# 7segLED.net
KiCad netlist of a schematic drawn in Altium Designer
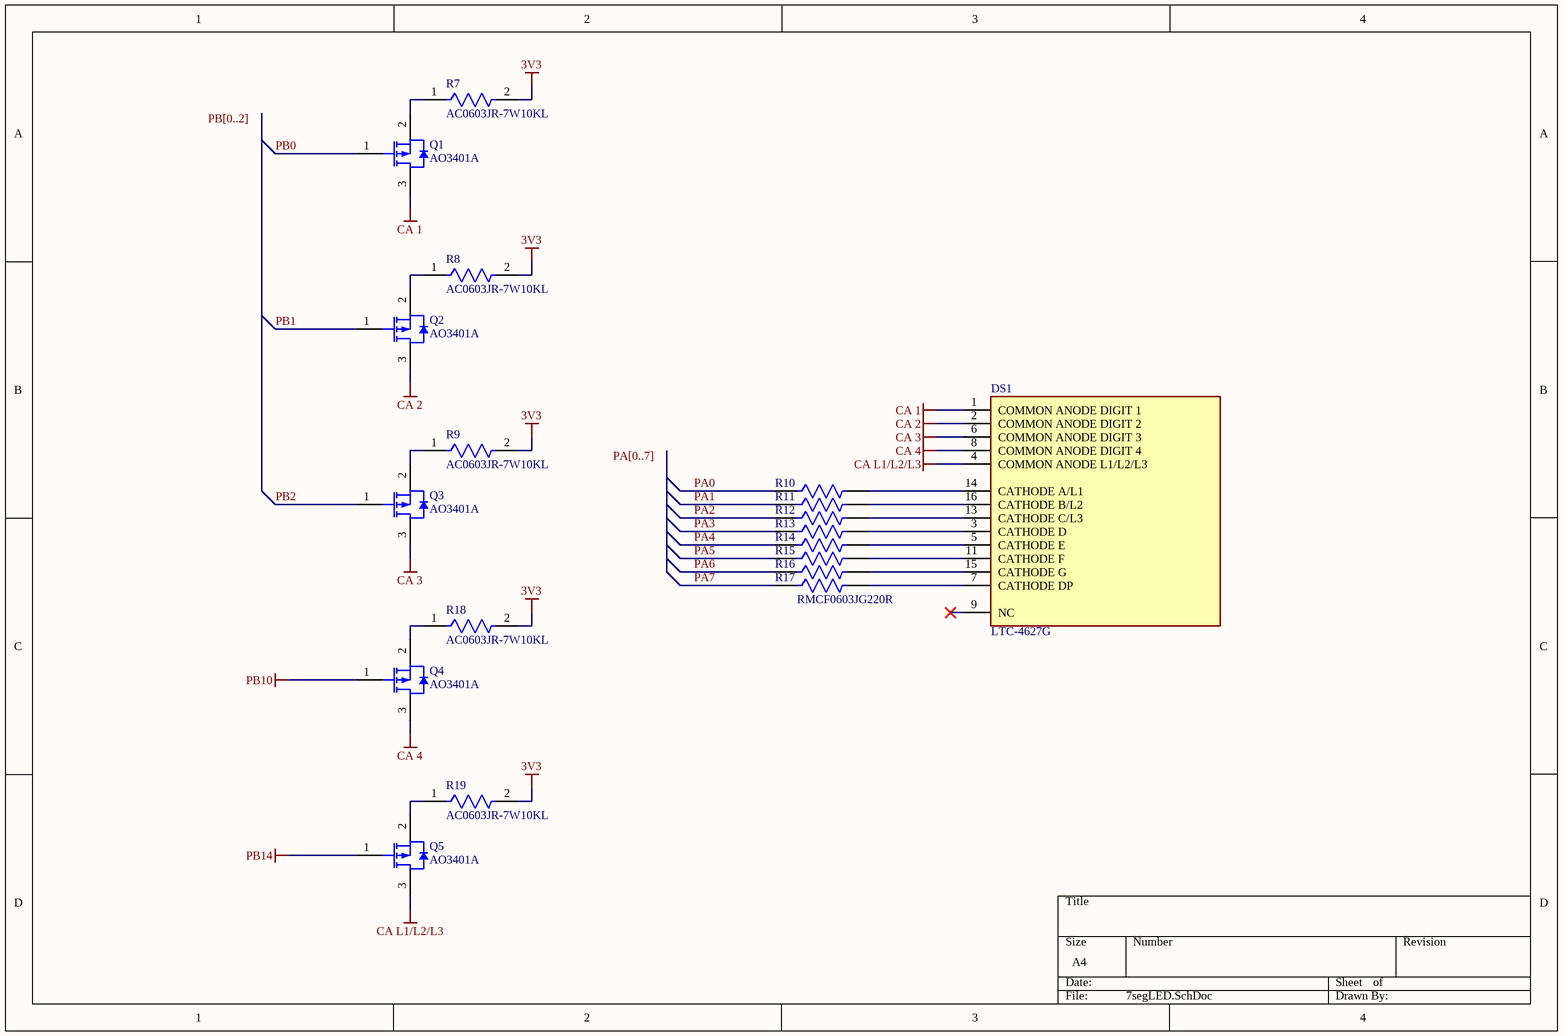
[diagram p0: 7segLED.SchDoc]

(export (version "E")
  (design (tool "Eeschema 10.0.6"))
  (components
    (comp (ref "DS1")
      (value "LTC-4627G")
      (footprint "FP-LTC-4627G-MFG")
      (description "LED 7-SEG 4DIGIT GRN 0.4\" CA")
      (fields
        (field (name "OCTOPART") "https://octopart.com/ltc-4627g-lite-on-8442722")
        (field (name "MANUFACTURER") "Lite-On")
      )
      (libsource (lib "Altium Content Vault") (part "4d055b40ff5d7e2a8d2cf02d3223e38"))
    )
    (comp (ref "Q1")
      (value "AO3401A")
      (footprint "AO-SOT-23-3L_V")
      (description "P-Channel MOSFET, 30 V, 4 A, -55 to 150 degC, 3-Pin SOT-23-3L, RoHS, Tape and Reel")
      (fields (field (name "MANUFACTURER") "Alpha and Omega"))
      (libsource (lib "Altium Content Vault") (part "PEMOS-GSD-3"))
    )
    (comp (ref "Q2")
      (value "AO3401A")
      (footprint "AO-SOT-23-3L_V")
      (description "P-Channel MOSFET, 30 V, 4 A, -55 to 150 degC, 3-Pin SOT-23-3L, RoHS, Tape and Reel")
      (fields (field (name "MANUFACTURER") "Alpha and Omega"))
      (libsource (lib "Altium Content Vault") (part "PEMOS-GSD-3"))
    )
    (comp (ref "Q3")
      (value "AO3401A")
      (footprint "AO-SOT-23-3L_V")
      (description "P-Channel MOSFET, 30 V, 4 A, -55 to 150 degC, 3-Pin SOT-23-3L, RoHS, Tape and Reel")
      (fields (field (name "MANUFACTURER") "Alpha and Omega"))
      (libsource (lib "Altium Content Vault") (part "PEMOS-GSD-3"))
    )
    (comp (ref "Q4")
      (value "AO3401A")
      (footprint "AO-SOT-23-3L_V")
      (description "P-Channel MOSFET, 30 V, 4 A, -55 to 150 degC, 3-Pin SOT-23-3L, RoHS, Tape and Reel")
      (fields (field (name "MANUFACTURER") "Alpha and Omega"))
      (libsource (lib "Altium Content Vault") (part "PEMOS-GSD-3"))
    )
    (comp (ref "Q5")
      (value "AO3401A")
      (footprint "AO-SOT-23-3L_V")
      (description "P-Channel MOSFET, 30 V, 4 A, -55 to 150 degC, 3-Pin SOT-23-3L, RoHS, Tape and Reel")
      (fields (field (name "MANUFACTURER") "Alpha and Omega"))
      (libsource (lib "Altium Content Vault") (part "PEMOS-GSD-3"))
    )
    (comp (ref "R7")
      (value "AC0603JR-7W10KL")
      (footprint "FP-AC0603-IPC_A")
      (description "RES 10kΩ 5.00% 0.2W 0603")
      (libsource (lib "") (part "1029c3af85768c4190bb7ad29bc67b5_1"))
    )
    (comp (ref "R8")
      (value "AC0603JR-7W10KL")
      (footprint "FP-AC0603-IPC_A")
      (description "RES 10kΩ 5.00% 0.2W 0603")
      (libsource (lib "") (part "1029c3af85768c4190bb7ad29bc67b5_1"))
    )
    (comp (ref "R9")
      (value "AC0603JR-7W10KL")
      (footprint "FP-AC0603-IPC_A")
      (description "RES 10kΩ 5.00% 0.2W 0603")
      (libsource (lib "") (part "1029c3af85768c4190bb7ad29bc67b5_1"))
    )
    (comp (ref "R10")
      (value "RMCF0603JG220R")
      (footprint "FP-RMCF0603-MFG")
      (description "220Ω ±5% 0.1W 0603 Thick Film Chip Resistor AEC-Q200 compliant")
      (fields (field (name "TOLERANCE") "5%"))
      (libsource (lib "Altium Content Vault") (part "1029c3af85768c4190bb7ad29bc67b5"))
    )
    (comp (ref "R11")
      (value "RMCF0603JG220R")
      (footprint "FP-RMCF0603-MFG")
      (description "220Ω ±5% 0.1W 0603 Thick Film Chip Resistor AEC-Q200 compliant")
      (fields (field (name "TOLERANCE") "5%"))
      (libsource (lib "Altium Content Vault") (part "1029c3af85768c4190bb7ad29bc67b5"))
    )
    (comp (ref "R12")
      (value "RMCF0603JG220R")
      (footprint "FP-RMCF0603-MFG")
      (description "220Ω ±5% 0.1W 0603 Thick Film Chip Resistor AEC-Q200 compliant")
      (fields (field (name "TOLERANCE") "5%"))
      (libsource (lib "Altium Content Vault") (part "1029c3af85768c4190bb7ad29bc67b5"))
    )
    (comp (ref "R13")
      (value "RMCF0603JG220R")
      (footprint "FP-RMCF0603-MFG")
      (description "220Ω ±5% 0.1W 0603 Thick Film Chip Resistor AEC-Q200 compliant")
      (fields (field (name "TOLERANCE") "5%"))
      (libsource (lib "Altium Content Vault") (part "1029c3af85768c4190bb7ad29bc67b5"))
    )
    (comp (ref "R14")
      (value "RMCF0603JG220R")
      (footprint "FP-RMCF0603-MFG")
      (description "220Ω ±5% 0.1W 0603 Thick Film Chip Resistor AEC-Q200 compliant")
      (fields (field (name "TOLERANCE") "5%"))
      (libsource (lib "Altium Content Vault") (part "1029c3af85768c4190bb7ad29bc67b5"))
    )
    (comp (ref "R15")
      (value "RMCF0603JG220R")
      (footprint "FP-RMCF0603-MFG")
      (description "220Ω ±5% 0.1W 0603 Thick Film Chip Resistor AEC-Q200 compliant")
      (fields (field (name "TOLERANCE") "5%"))
      (libsource (lib "Altium Content Vault") (part "1029c3af85768c4190bb7ad29bc67b5"))
    )
    (comp (ref "R16")
      (value "RMCF0603JG220R")
      (footprint "FP-RMCF0603-MFG")
      (description "220Ω ±5% 0.1W 0603 Thick Film Chip Resistor AEC-Q200 compliant")
      (fields (field (name "TOLERANCE") "5%"))
      (libsource (lib "Altium Content Vault") (part "1029c3af85768c4190bb7ad29bc67b5"))
    )
    (comp (ref "R17")
      (value "RMCF0603JG220R")
      (footprint "FP-RMCF0603-MFG")
      (description "220Ω ±5% 0.1W 0603 Thick Film Chip Resistor AEC-Q200 compliant")
      (fields (field (name "TOLERANCE") "5%"))
      (libsource (lib "Altium Content Vault") (part "1029c3af85768c4190bb7ad29bc67b5"))
    )
    (comp (ref "R18")
      (value "AC0603JR-7W10KL")
      (footprint "FP-AC0603-IPC_A")
      (description "RES 10kΩ 5.00% 0.2W 0603")
      (libsource (lib "") (part "1029c3af85768c4190bb7ad29bc67b5_1"))
    )
    (comp (ref "R19")
      (value "AC0603JR-7W10KL")
      (footprint "FP-AC0603-IPC_A")
      (description "RES 10kΩ 5.00% 0.2W 0603")
      (libsource (lib "") (part "1029c3af85768c4190bb7ad29bc67b5_1"))
    )
  )
  (nets
    (net (code "1") (name "/PA0") (class "Default")
      (node (ref "R10") (pin "1") (pinfunction "1_1") (pintype "passive"))
    )
    (net (code "2") (name "/PA1") (class "Default")
      (node (ref "R11") (pin "1") (pinfunction "1_1") (pintype "passive"))
    )
    (net (code "3") (name "/PA2") (class "Default")
      (node (ref "R12") (pin "1") (pinfunction "1_1") (pintype "passive"))
    )
    (net (code "4") (name "/PA3") (class "Default")
      (node (ref "R13") (pin "1") (pinfunction "1_1") (pintype "passive"))
    )
    (net (code "5") (name "/PA4") (class "Default")
      (node (ref "R14") (pin "1") (pinfunction "1_1") (pintype "passive"))
    )
    (net (code "6") (name "/PA5") (class "Default")
      (node (ref "R15") (pin "1") (pinfunction "1_1") (pintype "passive"))
    )
    (net (code "7") (name "/PA6") (class "Default")
      (node (ref "R16") (pin "1") (pinfunction "1_1") (pintype "passive"))
    )
    (net (code "8") (name "/PA7") (class "Default")
      (node (ref "R17") (pin "1") (pinfunction "1_1") (pintype "passive"))
    )
    (net (code "10") (name "/PB0") (class "Default")
      (node (ref "Q1") (pin "1") (pinfunction "GATE_1") (pintype "passive"))
    )
    (net (code "11") (name "/PB1") (class "Default")
      (node (ref "Q2") (pin "1") (pinfunction "GATE_1") (pintype "passive"))
    )
    (net (code "12") (name "/PB2") (class "Default")
      (node (ref "Q3") (pin "1") (pinfunction "GATE_1") (pintype "passive"))
    )
    (net (code "14") (name "3V3") (class "Default")
      (node (ref "R18") (pin "2") (pinfunction "2_2") (pintype "passive"))
      (node (ref "R19") (pin "2") (pinfunction "2_2") (pintype "passive"))
      (node (ref "R7") (pin "2") (pinfunction "2_2") (pintype "passive"))
      (node (ref "R8") (pin "2") (pinfunction "2_2") (pintype "passive"))
      (node (ref "R9") (pin "2") (pinfunction "2_2") (pintype "passive"))
    )
    (net (code "15") (name "CA 1") (class "Default")
      (node (ref "DS1") (pin "1") (pinfunction "COMMON_ANODE_DIGIT_1_1") (pintype "passive"))
      (node (ref "Q1") (pin "3") (pinfunction "DRAIN_3") (pintype "passive"))
    )
    (net (code "16") (name "CA 2") (class "Default")
      (node (ref "DS1") (pin "2") (pinfunction "COMMON_ANODE_DIGIT_2_2") (pintype "passive"))
      (node (ref "Q2") (pin "3") (pinfunction "DRAIN_3") (pintype "passive"))
    )
    (net (code "17") (name "CA 3") (class "Default")
      (node (ref "DS1") (pin "6") (pinfunction "COMMON_ANODE_DIGIT_3_6") (pintype "passive"))
      (node (ref "Q3") (pin "3") (pinfunction "DRAIN_3") (pintype "passive"))
    )
    (net (code "18") (name "CA 4") (class "Default")
      (node (ref "DS1") (pin "8") (pinfunction "COMMON_ANODE_DIGIT_4_8") (pintype "passive"))
      (node (ref "Q4") (pin "3") (pinfunction "DRAIN_3") (pintype "passive"))
    )
    (net (code "19") (name "CA L1{slash}L2{slash}L3") (class "Default")
      (node (ref "DS1") (pin "4") (pinfunction "COMMON_ANODE_L1/L2/L3_4") (pintype "passive"))
      (node (ref "Q5") (pin "3") (pinfunction "DRAIN_3") (pintype "passive"))
    )
    (net (code "20") (name "Net-(DS1-CATHODE_A{slash}L1)") (class "Default")
      (node (ref "DS1") (pin "14") (pinfunction "CATHODE_A/L1_14") (pintype "passive"))
      (node (ref "R10") (pin "2") (pinfunction "2_2") (pintype "passive"))
    )
    (net (code "21") (name "Net-(DS1-CATHODE_B{slash}L2)") (class "Default")
      (node (ref "DS1") (pin "16") (pinfunction "CATHODE_B/L2_16") (pintype "passive"))
      (node (ref "R11") (pin "2") (pinfunction "2_2") (pintype "passive"))
    )
    (net (code "22") (name "Net-(DS1-CATHODE_C{slash}L3)") (class "Default")
      (node (ref "DS1") (pin "13") (pinfunction "CATHODE_C/L3_13") (pintype "passive"))
      (node (ref "R12") (pin "2") (pinfunction "2_2") (pintype "passive"))
    )
    (net (code "23") (name "Net-(DS1-CATHODE_D)") (class "Default")
      (node (ref "DS1") (pin "3") (pinfunction "CATHODE_D_3") (pintype "passive"))
      (node (ref "R13") (pin "2") (pinfunction "2_2") (pintype "passive"))
    )
    (net (code "24") (name "Net-(DS1-CATHODE_DP)") (class "Default")
      (node (ref "DS1") (pin "7") (pinfunction "CATHODE_DP_7") (pintype "passive"))
      (node (ref "R17") (pin "2") (pinfunction "2_2") (pintype "passive"))
    )
    (net (code "25") (name "Net-(DS1-CATHODE_E)") (class "Default")
      (node (ref "DS1") (pin "5") (pinfunction "CATHODE_E_5") (pintype "passive"))
      (node (ref "R14") (pin "2") (pinfunction "2_2") (pintype "passive"))
    )
    (net (code "26") (name "Net-(DS1-CATHODE_F)") (class "Default")
      (node (ref "DS1") (pin "11") (pinfunction "CATHODE_F_11") (pintype "passive"))
      (node (ref "R15") (pin "2") (pinfunction "2_2") (pintype "passive"))
    )
    (net (code "27") (name "Net-(DS1-CATHODE_G)") (class "Default")
      (node (ref "DS1") (pin "15") (pinfunction "CATHODE_G_15") (pintype "passive"))
      (node (ref "R16") (pin "2") (pinfunction "2_2") (pintype "passive"))
    )
    (net (code "28") (name "Net-(Q1-SOURCE)") (class "Default")
      (node (ref "Q1") (pin "2") (pinfunction "SOURCE_2") (pintype "passive"))
      (node (ref "R7") (pin "1") (pinfunction "1_1") (pintype "passive"))
    )
    (net (code "29") (name "Net-(Q2-SOURCE)") (class "Default")
      (node (ref "Q2") (pin "2") (pinfunction "SOURCE_2") (pintype "passive"))
      (node (ref "R8") (pin "1") (pinfunction "1_1") (pintype "passive"))
    )
    (net (code "30") (name "Net-(Q3-SOURCE)") (class "Default")
      (node (ref "Q3") (pin "2") (pinfunction "SOURCE_2") (pintype "passive"))
      (node (ref "R9") (pin "1") (pinfunction "1_1") (pintype "passive"))
    )
    (net (code "31") (name "Net-(Q4-SOURCE)") (class "Default")
      (node (ref "Q4") (pin "2") (pinfunction "SOURCE_2") (pintype "passive"))
      (node (ref "R18") (pin "1") (pinfunction "1_1") (pintype "passive"))
    )
    (net (code "32") (name "Net-(Q5-SOURCE)") (class "Default")
      (node (ref "Q5") (pin "2") (pinfunction "SOURCE_2") (pintype "passive"))
      (node (ref "R19") (pin "1") (pinfunction "1_1") (pintype "passive"))
    )
    (net (code "33") (name "PB10") (class "Default")
      (node (ref "Q4") (pin "1") (pinfunction "GATE_1") (pintype "passive"))
    )
    (net (code "34") (name "PB14") (class "Default")
      (node (ref "Q5") (pin "1") (pinfunction "GATE_1") (pintype "passive"))
    )
    (net (code "35") (name "unconnected-(DS1-NC-Pad9)") (class "Default")
      (node (ref "DS1") (pin "9") (pinfunction "NC_9") (pintype "passive+no_connect"))
    )
  )
)
